# EST_MainV20_Input.net
KiCad netlist of a schematic drawn in Altium Designer
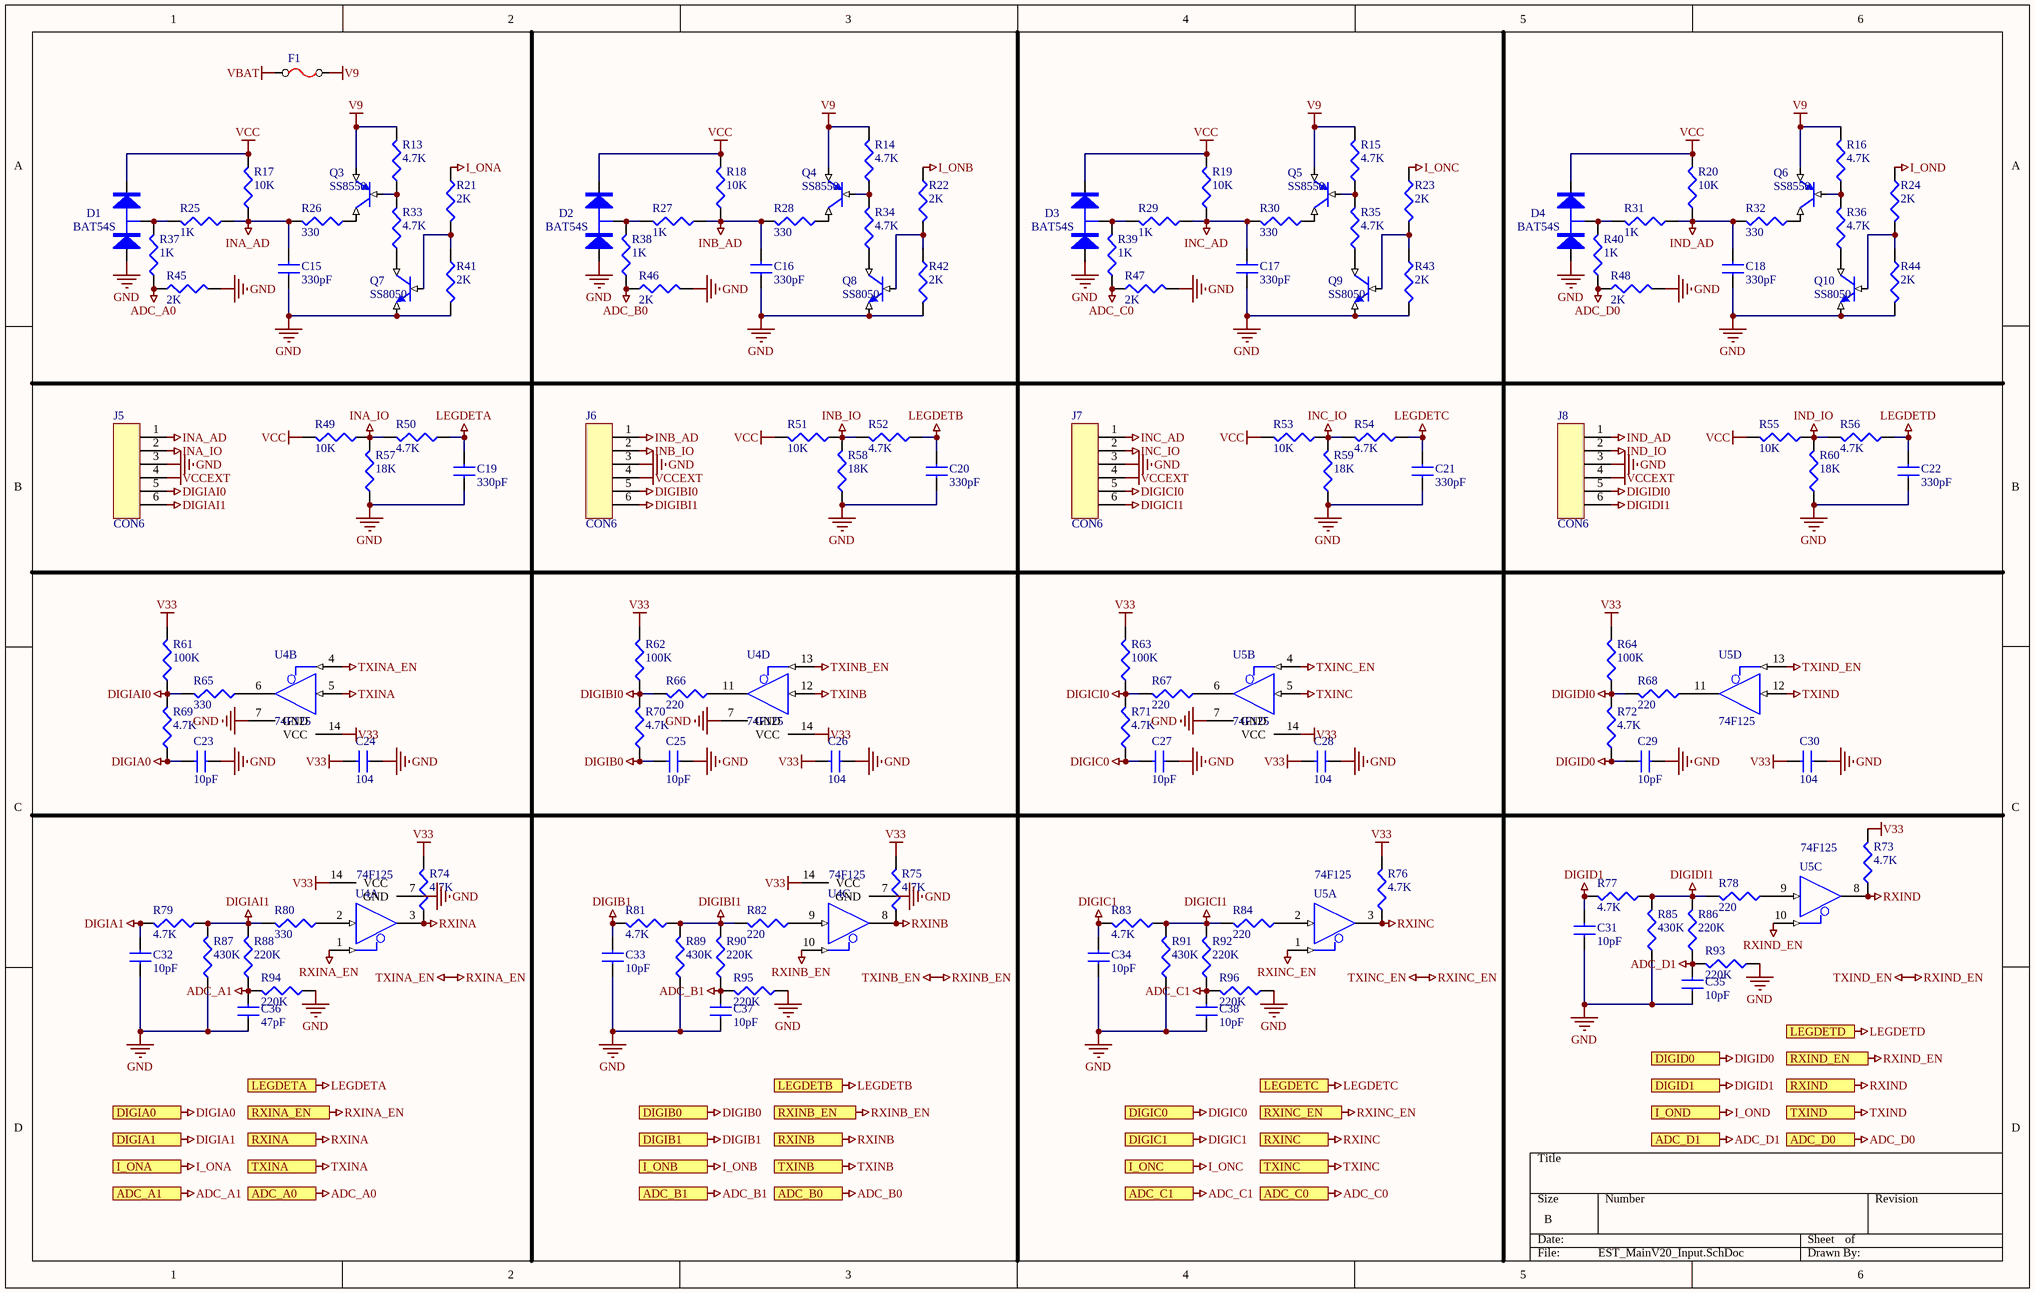
[diagram p0: EST_MainV20_Input.SchDoc]

(export (version "E")
  (design (tool "Eeschema 10.0.6"))
  (components
    (comp (ref "C15")
      (value "330pF")
      (footprint "CAP_0603")
      (description "Capacitor")
      (libsource (lib "模拟器件") (part "CAP"))
    )
    (comp (ref "C16")
      (value "330pF")
      (footprint "CAP_0603")
      (description "Capacitor")
      (libsource (lib "模拟器件") (part "CAP"))
    )
    (comp (ref "C17")
      (value "330pF")
      (footprint "CAP_0603")
      (description "Capacitor")
      (libsource (lib "模拟器件") (part "CAP"))
    )
    (comp (ref "C18")
      (value "330pF")
      (footprint "CAP_0603")
      (description "Capacitor")
      (libsource (lib "模拟器件") (part "CAP"))
    )
    (comp (ref "C19")
      (value "330pF")
      (footprint "CAP_0603")
      (description "Capacitor")
      (libsource (lib "模拟器件") (part "CAP"))
    )
    (comp (ref "C20")
      (value "330pF")
      (footprint "CAP_0603")
      (description "Capacitor")
      (libsource (lib "模拟器件") (part "CAP"))
    )
    (comp (ref "C21")
      (value "330pF")
      (footprint "CAP_0603")
      (description "Capacitor")
      (libsource (lib "模拟器件") (part "CAP"))
    )
    (comp (ref "C22")
      (value "330pF")
      (footprint "CAP_0603")
      (description "Capacitor")
      (libsource (lib "模拟器件") (part "CAP"))
    )
    (comp (ref "C23")
      (value "10pF")
      (footprint "CAP_0603")
      (description "Capacitor")
      (libsource (lib "模拟器件") (part "CAP"))
    )
    (comp (ref "C24")
      (value "104")
      (footprint "CAP_0603")
      (description "Capacitor")
      (libsource (lib "模拟器件") (part "CAP"))
    )
    (comp (ref "C25")
      (value "10pF")
      (footprint "CAP_0603")
      (description "Capacitor")
      (libsource (lib "模拟器件") (part "CAP"))
    )
    (comp (ref "C26")
      (value "104")
      (footprint "CAP_0603")
      (description "Capacitor")
      (libsource (lib "模拟器件") (part "CAP"))
    )
    (comp (ref "C27")
      (value "10pF")
      (footprint "CAP_0603")
      (description "Capacitor")
      (libsource (lib "模拟器件") (part "CAP"))
    )
    (comp (ref "C28")
      (value "104")
      (footprint "CAP_0603")
      (description "Capacitor")
      (libsource (lib "模拟器件") (part "CAP"))
    )
    (comp (ref "C29")
      (value "10pF")
      (footprint "CAP_0603")
      (description "Capacitor")
      (libsource (lib "模拟器件") (part "CAP"))
    )
    (comp (ref "C30")
      (value "104")
      (footprint "CAP_0603")
      (description "Capacitor")
      (libsource (lib "模拟器件") (part "CAP"))
    )
    (comp (ref "C31")
      (value "10pF")
      (footprint "CAP_0603")
      (description "Capacitor")
      (libsource (lib "模拟器件") (part "CAP"))
    )
    (comp (ref "C32")
      (value "10pF")
      (footprint "CAP_0603")
      (description "Capacitor")
      (libsource (lib "模拟器件") (part "CAP"))
    )
    (comp (ref "C33")
      (value "10pF")
      (footprint "CAP_0603")
      (description "Capacitor")
      (libsource (lib "模拟器件") (part "CAP"))
    )
    (comp (ref "C34")
      (value "10pF")
      (footprint "CAP_0603")
      (description "Capacitor")
      (libsource (lib "模拟器件") (part "CAP"))
    )
    (comp (ref "C35")
      (value "10pF")
      (footprint "CAP_0603")
      (description "Capacitor")
      (libsource (lib "模拟器件") (part "CAP"))
    )
    (comp (ref "C36")
      (value "47pF")
      (footprint "CAP_0603")
      (description "Capacitor")
      (libsource (lib "模拟器件") (part "CAP"))
    )
    (comp (ref "C37")
      (value "10pF")
      (footprint "CAP_0603")
      (description "Capacitor")
      (libsource (lib "模拟器件") (part "CAP"))
    )
    (comp (ref "C38")
      (value "10pF")
      (footprint "CAP_0603")
      (description "Capacitor")
      (libsource (lib "模拟器件") (part "CAP"))
    )
    (comp (ref "D1")
      (value "BAT54S")
      (footprint "BAT54S")
      (description "DIODE BRIDGE")
      (libsource (lib "模拟器件") (part "BANQIAO-A"))
    )
    (comp (ref "D2")
      (value "BAT54S")
      (footprint "BAT54S")
      (description "DIODE BRIDGE")
      (libsource (lib "模拟器件") (part "BANQIAO-A"))
    )
    (comp (ref "D3")
      (value "BAT54S")
      (footprint "BAT54S")
      (description "DIODE BRIDGE")
      (libsource (lib "模拟器件") (part "BANQIAO-A"))
    )
    (comp (ref "D4")
      (value "BAT54S")
      (footprint "BAT54S")
      (description "DIODE BRIDGE")
      (libsource (lib "模拟器件") (part "BANQIAO-A"))
    )
    (comp (ref "F1")
      (value "FUSE")
      (footprint "1812")
      (description "Fuse")
      (libsource (lib "模拟器件") (part "FUSE"))
    )
    (comp (ref "J5") (value "CON6") (footprint "Lego_RJ11") (libsource (lib "模拟器件") (part "CON6")))
    (comp (ref "J6") (value "CON6") (footprint "Lego_RJ11") (libsource (lib "模拟器件") (part "CON6")))
    (comp (ref "J7") (value "CON6") (footprint "Lego_RJ11") (libsource (lib "模拟器件") (part "CON6")))
    (comp (ref "J8") (value "CON6") (footprint "Lego_RJ11") (libsource (lib "模拟器件") (part "CON6")))
    (comp (ref "Q3")
      (value "SS8550")
      (footprint "8050SMD")
      (description "triode")
      (libsource (lib "模拟器件") (part "PNP"))
    )
    (comp (ref "Q4")
      (value "SS8550")
      (footprint "8050SMD")
      (description "triode")
      (libsource (lib "模拟器件") (part "PNP"))
    )
    (comp (ref "Q5")
      (value "SS8550")
      (footprint "8050SMD")
      (description "triode")
      (libsource (lib "模拟器件") (part "PNP"))
    )
    (comp (ref "Q6")
      (value "SS8550")
      (footprint "8050SMD")
      (description "triode")
      (libsource (lib "模拟器件") (part "PNP"))
    )
    (comp (ref "Q7")
      (value "SS8050")
      (footprint "8050SMD")
      (description "triode")
      (libsource (lib "模拟器件") (part "NPN"))
    )
    (comp (ref "Q8")
      (value "SS8050")
      (footprint "8050SMD")
      (description "triode")
      (libsource (lib "模拟器件") (part "NPN"))
    )
    (comp (ref "Q9")
      (value "SS8050")
      (footprint "8050SMD")
      (description "triode")
      (libsource (lib "模拟器件") (part "NPN"))
    )
    (comp (ref "Q10")
      (value "SS8050")
      (footprint "8050SMD")
      (description "triode")
      (libsource (lib "模拟器件") (part "NPN"))
    )
    (comp (ref "R13")
      (value "4.7K")
      (footprint "RES_0603")
      (description "Resistor")
      (libsource (lib "模拟器件") (part "RES"))
    )
    (comp (ref "R14")
      (value "4.7K")
      (footprint "RES_0603")
      (description "Resistor")
      (libsource (lib "模拟器件") (part "RES"))
    )
    (comp (ref "R15")
      (value "4.7K")
      (footprint "RES_0603")
      (description "Resistor")
      (libsource (lib "模拟器件") (part "RES"))
    )
    (comp (ref "R16")
      (value "4.7K")
      (footprint "RES_0603")
      (description "Resistor")
      (libsource (lib "模拟器件") (part "RES"))
    )
    (comp (ref "R17")
      (value "10K")
      (footprint "RES_0603")
      (description "Resistor")
      (libsource (lib "模拟器件") (part "RES"))
    )
    (comp (ref "R18")
      (value "10K")
      (footprint "RES_0603")
      (description "Resistor")
      (libsource (lib "模拟器件") (part "RES"))
    )
    (comp (ref "R19")
      (value "10K")
      (footprint "RES_0603")
      (description "Resistor")
      (libsource (lib "模拟器件") (part "RES"))
    )
    (comp (ref "R20")
      (value "10K")
      (footprint "RES_0603")
      (description "Resistor")
      (libsource (lib "模拟器件") (part "RES"))
    )
    (comp (ref "R21")
      (value "2K")
      (footprint "RES_0603")
      (description "Resistor")
      (libsource (lib "模拟器件") (part "RES"))
    )
    (comp (ref "R22")
      (value "2K")
      (footprint "RES_0603")
      (description "Resistor")
      (libsource (lib "模拟器件") (part "RES"))
    )
    (comp (ref "R23")
      (value "2K")
      (footprint "RES_0603")
      (description "Resistor")
      (libsource (lib "模拟器件") (part "RES"))
    )
    (comp (ref "R24")
      (value "2K")
      (footprint "RES_0603")
      (description "Resistor")
      (libsource (lib "模拟器件") (part "RES"))
    )
    (comp (ref "R25")
      (value "1K")
      (footprint "RES_0603")
      (description "Resistor")
      (libsource (lib "模拟器件") (part "RES"))
    )
    (comp (ref "R26")
      (value "330")
      (footprint "RES_0603")
      (description "Resistor")
      (libsource (lib "模拟器件") (part "RES"))
    )
    (comp (ref "R27")
      (value "1K")
      (footprint "RES_0603")
      (description "Resistor")
      (libsource (lib "模拟器件") (part "RES"))
    )
    (comp (ref "R28")
      (value "330")
      (footprint "RES_0603")
      (description "Resistor")
      (libsource (lib "模拟器件") (part "RES"))
    )
    (comp (ref "R29")
      (value "1K")
      (footprint "RES_0603")
      (description "Resistor")
      (libsource (lib "模拟器件") (part "RES"))
    )
    (comp (ref "R30")
      (value "330")
      (footprint "RES_0603")
      (description "Resistor")
      (libsource (lib "模拟器件") (part "RES"))
    )
    (comp (ref "R31")
      (value "1K")
      (footprint "RES_0603")
      (description "Resistor")
      (libsource (lib "模拟器件") (part "RES"))
    )
    (comp (ref "R32")
      (value "330")
      (footprint "RES_0603")
      (description "Resistor")
      (libsource (lib "模拟器件") (part "RES"))
    )
    (comp (ref "R33")
      (value "4.7K")
      (footprint "RES_0603")
      (description "Resistor")
      (libsource (lib "模拟器件") (part "RES"))
    )
    (comp (ref "R34")
      (value "4.7K")
      (footprint "RES_0603")
      (description "Resistor")
      (libsource (lib "模拟器件") (part "RES"))
    )
    (comp (ref "R35")
      (value "4.7K")
      (footprint "RES_0603")
      (description "Resistor")
      (libsource (lib "模拟器件") (part "RES"))
    )
    (comp (ref "R36")
      (value "4.7K")
      (footprint "RES_0603")
      (description "Resistor")
      (libsource (lib "模拟器件") (part "RES"))
    )
    (comp (ref "R37")
      (value "1K")
      (footprint "RES_0603")
      (description "Resistor")
      (libsource (lib "模拟器件") (part "RES"))
    )
    (comp (ref "R38")
      (value "1K")
      (footprint "RES_0603")
      (description "Resistor")
      (libsource (lib "模拟器件") (part "RES"))
    )
    (comp (ref "R39")
      (value "1K")
      (footprint "RES_0603")
      (description "Resistor")
      (libsource (lib "模拟器件") (part "RES"))
    )
    (comp (ref "R40")
      (value "1K")
      (footprint "RES_0603")
      (description "Resistor")
      (libsource (lib "模拟器件") (part "RES"))
    )
    (comp (ref "R41")
      (value "2K")
      (footprint "RES_0603")
      (description "Resistor")
      (libsource (lib "模拟器件") (part "RES"))
    )
    (comp (ref "R42")
      (value "2K")
      (footprint "RES_0603")
      (description "Resistor")
      (libsource (lib "模拟器件") (part "RES"))
    )
    (comp (ref "R43")
      (value "2K")
      (footprint "RES_0603")
      (description "Resistor")
      (libsource (lib "模拟器件") (part "RES"))
    )
    (comp (ref "R44")
      (value "2K")
      (footprint "RES_0603")
      (description "Resistor")
      (libsource (lib "模拟器件") (part "RES"))
    )
    (comp (ref "R45")
      (value "2K")
      (footprint "RES_0603")
      (description "Resistor")
      (libsource (lib "模拟器件") (part "RES"))
    )
    (comp (ref "R46")
      (value "2K")
      (footprint "RES_0603")
      (description "Resistor")
      (libsource (lib "模拟器件") (part "RES"))
    )
    (comp (ref "R47")
      (value "2K")
      (footprint "RES_0603")
      (description "Resistor")
      (libsource (lib "模拟器件") (part "RES"))
    )
    (comp (ref "R48")
      (value "2K")
      (footprint "RES_0603")
      (description "Resistor")
      (libsource (lib "模拟器件") (part "RES"))
    )
    (comp (ref "R49")
      (value "10K")
      (footprint "RES_0603")
      (description "Resistor")
      (libsource (lib "模拟器件") (part "RES"))
    )
    (comp (ref "R50")
      (value "4.7K")
      (footprint "RES_0603")
      (description "Resistor")
      (libsource (lib "模拟器件") (part "RES"))
    )
    (comp (ref "R51")
      (value "10K")
      (footprint "RES_0603")
      (description "Resistor")
      (libsource (lib "模拟器件") (part "RES"))
    )
    (comp (ref "R52")
      (value "4.7K")
      (footprint "RES_0603")
      (description "Resistor")
      (libsource (lib "模拟器件") (part "RES"))
    )
    (comp (ref "R53")
      (value "10K")
      (footprint "RES_0603")
      (description "Resistor")
      (libsource (lib "模拟器件") (part "RES"))
    )
    (comp (ref "R54")
      (value "4.7K")
      (footprint "RES_0603")
      (description "Resistor")
      (libsource (lib "模拟器件") (part "RES"))
    )
    (comp (ref "R55")
      (value "10K")
      (footprint "RES_0603")
      (description "Resistor")
      (libsource (lib "模拟器件") (part "RES"))
    )
    (comp (ref "R56")
      (value "4.7K")
      (footprint "RES_0603")
      (description "Resistor")
      (libsource (lib "模拟器件") (part "RES"))
    )
    (comp (ref "R57")
      (value "18K")
      (footprint "RES_0603")
      (description "Resistor")
      (libsource (lib "模拟器件") (part "RES"))
    )
    (comp (ref "R58")
      (value "18K")
      (footprint "RES_0603")
      (description "Resistor")
      (libsource (lib "模拟器件") (part "RES"))
    )
    (comp (ref "R59")
      (value "18K")
      (footprint "RES_0603")
      (description "Resistor")
      (libsource (lib "模拟器件") (part "RES"))
    )
    (comp (ref "R60")
      (value "18K")
      (footprint "RES_0603")
      (description "Resistor")
      (libsource (lib "模拟器件") (part "RES"))
    )
    (comp (ref "R61")
      (value "100K")
      (footprint "RES_0603")
      (description "Resistor")
      (libsource (lib "模拟器件") (part "RES"))
    )
    (comp (ref "R62")
      (value "100K")
      (footprint "RES_0603")
      (description "Resistor")
      (libsource (lib "模拟器件") (part "RES"))
    )
    (comp (ref "R63")
      (value "100K")
      (footprint "RES_0603")
      (description "Resistor")
      (libsource (lib "模拟器件") (part "RES"))
    )
    (comp (ref "R64")
      (value "100K")
      (footprint "RES_0603")
      (description "Resistor")
      (libsource (lib "模拟器件") (part "RES"))
    )
    (comp (ref "R65")
      (value "330")
      (footprint "RES_0603")
      (description "Resistor")
      (libsource (lib "模拟器件") (part "RES"))
    )
    (comp (ref "R66")
      (value "220")
      (footprint "RES_0603")
      (description "Resistor")
      (libsource (lib "模拟器件") (part "RES"))
    )
    (comp (ref "R67")
      (value "220")
      (footprint "RES_0603")
      (description "Resistor")
      (libsource (lib "模拟器件") (part "RES"))
    )
    (comp (ref "R68")
      (value "220")
      (footprint "RES_0603")
      (description "Resistor")
      (libsource (lib "模拟器件") (part "RES"))
    )
    (comp (ref "R69")
      (value "4.7K")
      (footprint "RES_0603")
      (description "Resistor")
      (libsource (lib "模拟器件") (part "RES"))
    )
    (comp (ref "R70")
      (value "4.7K")
      (footprint "RES_0603")
      (description "Resistor")
      (libsource (lib "模拟器件") (part "RES"))
    )
    (comp (ref "R71")
      (value "4.7K")
      (footprint "RES_0603")
      (description "Resistor")
      (libsource (lib "模拟器件") (part "RES"))
    )
    (comp (ref "R72")
      (value "4.7K")
      (footprint "RES_0603")
      (description "Resistor")
      (libsource (lib "模拟器件") (part "RES"))
    )
    (comp (ref "R73")
      (value "4.7K")
      (footprint "RES_0603")
      (description "Resistor")
      (libsource (lib "模拟器件") (part "RES"))
    )
    (comp (ref "R74")
      (value "4.7K")
      (footprint "RES_0603")
      (description "Resistor")
      (libsource (lib "模拟器件") (part "RES"))
    )
    (comp (ref "R75")
      (value "4.7K")
      (footprint "RES_0603")
      (description "Resistor")
      (libsource (lib "模拟器件") (part "RES"))
    )
    (comp (ref "R76")
      (value "4.7K")
      (footprint "RES_0603")
      (description "Resistor")
      (libsource (lib "模拟器件") (part "RES"))
    )
    (comp (ref "R77")
      (value "4.7K")
      (footprint "RES_0603")
      (description "Resistor")
      (libsource (lib "模拟器件") (part "RES"))
    )
    (comp (ref "R78")
      (value "220")
      (footprint "RES_0603")
      (description "Resistor")
      (libsource (lib "模拟器件") (part "RES"))
    )
    (comp (ref "R79")
      (value "4.7K")
      (footprint "RES_0603")
      (description "Resistor")
      (libsource (lib "模拟器件") (part "RES"))
    )
    (comp (ref "R80")
      (value "330")
      (footprint "RES_0603")
      (description "Resistor")
      (libsource (lib "模拟器件") (part "RES"))
    )
    (comp (ref "R81")
      (value "4.7K")
      (footprint "RES_0603")
      (description "Resistor")
      (libsource (lib "模拟器件") (part "RES"))
    )
    (comp (ref "R82")
      (value "220")
      (footprint "RES_0603")
      (description "Resistor")
      (libsource (lib "模拟器件") (part "RES"))
    )
    (comp (ref "R83")
      (value "4.7K")
      (footprint "RES_0603")
      (description "Resistor")
      (libsource (lib "模拟器件") (part "RES"))
    )
    (comp (ref "R84")
      (value "220")
      (footprint "RES_0603")
      (description "Resistor")
      (libsource (lib "模拟器件") (part "RES"))
    )
    (comp (ref "R85")
      (value "430K")
      (footprint "RES_0603")
      (description "Resistor")
      (libsource (lib "模拟器件") (part "RES"))
    )
    (comp (ref "R86")
      (value "220K")
      (footprint "RES_0603")
      (description "Resistor")
      (libsource (lib "模拟器件") (part "RES"))
    )
    (comp (ref "R87")
      (value "430K")
      (footprint "RES_0603")
      (description "Resistor")
      (libsource (lib "模拟器件") (part "RES"))
    )
    (comp (ref "R88")
      (value "220K")
      (footprint "RES_0603")
      (description "Resistor")
      (libsource (lib "模拟器件") (part "RES"))
    )
    (comp (ref "R89")
      (value "430K")
      (footprint "RES_0603")
      (description "Resistor")
      (libsource (lib "模拟器件") (part "RES"))
    )
    (comp (ref "R90")
      (value "220K")
      (footprint "RES_0603")
      (description "Resistor")
      (libsource (lib "模拟器件") (part "RES"))
    )
    (comp (ref "R91")
      (value "430K")
      (footprint "RES_0603")
      (description "Resistor")
      (libsource (lib "模拟器件") (part "RES"))
    )
    (comp (ref "R92")
      (value "220K")
      (footprint "RES_0603")
      (description "Resistor")
      (libsource (lib "模拟器件") (part "RES"))
    )
    (comp (ref "R93")
      (value "220K")
      (footprint "RES_0603")
      (description "Resistor")
      (libsource (lib "模拟器件") (part "RES"))
    )
    (comp (ref "R94")
      (value "220K")
      (footprint "RES_0603")
      (description "Resistor")
      (libsource (lib "模拟器件") (part "RES"))
    )
    (comp (ref "R95")
      (value "220K")
      (footprint "RES_0603")
      (description "Resistor")
      (libsource (lib "模拟器件") (part "RES"))
    )
    (comp (ref "R96")
      (value "220K")
      (footprint "RES_0603")
      (description "Resistor")
      (libsource (lib "模拟器件") (part "RES"))
    )
    (comp (ref "U4")
      (value "74F125")
      (footprint "TSSOP14")
      (description "Quad Bus Buffer Gate with 3-State Output")
      (libsource (lib "TTL") (part "74F125"))
    )
    (comp (ref "U5")
      (value "74F125")
      (footprint "TSSOP14")
      (description "Quad Bus Buffer Gate with 3-State Output")
      (libsource (lib "TTL") (part "74F125"))
    )
  )
  (nets
    (net (code "1") (name "ADC_A0") (class "Default")
      (node (ref "R37") (pin "2") (pinfunction "BOT_2") (pintype "passive"))
      (node (ref "R45") (pin "2") (pinfunction "BOT_2") (pintype "passive"))
    )
    (net (code "2") (name "ADC_A1") (class "Default")
      (node (ref "C36") (pin "2") (pinfunction "2_2") (pintype "passive"))
      (node (ref "R88") (pin "2") (pinfunction "BOT_2") (pintype "passive"))
      (node (ref "R94") (pin "1") (pinfunction "TOP_1") (pintype "passive"))
    )
    (net (code "3") (name "ADC_B0") (class "Default")
      (node (ref "R38") (pin "2") (pinfunction "BOT_2") (pintype "passive"))
      (node (ref "R46") (pin "2") (pinfunction "BOT_2") (pintype "passive"))
    )
    (net (code "4") (name "ADC_B1") (class "Default")
      (node (ref "C37") (pin "2") (pinfunction "2_2") (pintype "passive"))
      (node (ref "R90") (pin "2") (pinfunction "BOT_2") (pintype "passive"))
      (node (ref "R95") (pin "1") (pinfunction "TOP_1") (pintype "passive"))
    )
    (net (code "5") (name "ADC_C0") (class "Default")
      (node (ref "R39") (pin "2") (pinfunction "BOT_2") (pintype "passive"))
      (node (ref "R47") (pin "2") (pinfunction "BOT_2") (pintype "passive"))
    )
    (net (code "6") (name "ADC_C1") (class "Default")
      (node (ref "C38") (pin "2") (pinfunction "2_2") (pintype "passive"))
      (node (ref "R92") (pin "2") (pinfunction "BOT_2") (pintype "passive"))
      (node (ref "R96") (pin "1") (pinfunction "TOP_1") (pintype "passive"))
    )
    (net (code "7") (name "ADC_D0") (class "Default")
      (node (ref "R40") (pin "2") (pinfunction "BOT_2") (pintype "passive"))
      (node (ref "R48") (pin "2") (pinfunction "BOT_2") (pintype "passive"))
    )
    (net (code "8") (name "ADC_D1") (class "Default")
      (node (ref "C35") (pin "2") (pinfunction "2_2") (pintype "passive"))
      (node (ref "R86") (pin "2") (pinfunction "BOT_2") (pintype "passive"))
      (node (ref "R93") (pin "1") (pinfunction "TOP_1") (pintype "passive"))
    )
    (net (code "9") (name "DIGIA0") (class "Default")
      (node (ref "C23") (pin "1") (pinfunction "1_1") (pintype "passive"))
      (node (ref "R69") (pin "2") (pinfunction "BOT_2") (pintype "passive"))
    )
    (net (code "10") (name "DIGIA1") (class "Default")
      (node (ref "C32") (pin "2") (pinfunction "2_2") (pintype "passive"))
      (node (ref "R79") (pin "1") (pinfunction "TOP_1") (pintype "passive"))
    )
    (net (code "11") (name "DIGIAI0") (class "Default")
      (node (ref "J5") (pin "5") (pinfunction "5_5") (pintype "passive"))
      (node (ref "R61") (pin "2") (pinfunction "BOT_2") (pintype "passive"))
      (node (ref "R65") (pin "1") (pinfunction "TOP_1") (pintype "passive"))
      (node (ref "R69") (pin "1") (pinfunction "TOP_1") (pintype "passive"))
    )
    (net (code "12") (name "DIGIAI1") (class "Default")
      (node (ref "J5") (pin "6") (pinfunction "6_6") (pintype "passive"))
      (node (ref "R79") (pin "2") (pinfunction "BOT_2") (pintype "passive"))
      (node (ref "R80") (pin "1") (pinfunction "TOP_1") (pintype "passive"))
      (node (ref "R87") (pin "1") (pinfunction "TOP_1") (pintype "passive"))
      (node (ref "R88") (pin "1") (pinfunction "TOP_1") (pintype "passive"))
    )
    (net (code "13") (name "DIGIB0") (class "Default")
      (node (ref "C25") (pin "1") (pinfunction "1_1") (pintype "passive"))
      (node (ref "R70") (pin "2") (pinfunction "BOT_2") (pintype "passive"))
    )
    (net (code "14") (name "DIGIB1") (class "Default")
      (node (ref "C33") (pin "2") (pinfunction "2_2") (pintype "passive"))
      (node (ref "R81") (pin "1") (pinfunction "TOP_1") (pintype "passive"))
    )
    (net (code "15") (name "DIGIBI0") (class "Default")
      (node (ref "J6") (pin "5") (pinfunction "5_5") (pintype "passive"))
      (node (ref "R62") (pin "2") (pinfunction "BOT_2") (pintype "passive"))
      (node (ref "R66") (pin "1") (pinfunction "TOP_1") (pintype "passive"))
      (node (ref "R70") (pin "1") (pinfunction "TOP_1") (pintype "passive"))
    )
    (net (code "16") (name "DIGIBI1") (class "Default")
      (node (ref "J6") (pin "6") (pinfunction "6_6") (pintype "passive"))
      (node (ref "R81") (pin "2") (pinfunction "BOT_2") (pintype "passive"))
      (node (ref "R82") (pin "1") (pinfunction "TOP_1") (pintype "passive"))
      (node (ref "R89") (pin "1") (pinfunction "TOP_1") (pintype "passive"))
      (node (ref "R90") (pin "1") (pinfunction "TOP_1") (pintype "passive"))
    )
    (net (code "17") (name "DIGIC0") (class "Default")
      (node (ref "C27") (pin "1") (pinfunction "1_1") (pintype "passive"))
      (node (ref "R71") (pin "2") (pinfunction "BOT_2") (pintype "passive"))
    )
    (net (code "18") (name "DIGIC1") (class "Default")
      (node (ref "C34") (pin "2") (pinfunction "2_2") (pintype "passive"))
      (node (ref "R83") (pin "1") (pinfunction "TOP_1") (pintype "passive"))
    )
    (net (code "19") (name "DIGICI0") (class "Default")
      (node (ref "J7") (pin "5") (pinfunction "5_5") (pintype "passive"))
      (node (ref "R63") (pin "2") (pinfunction "BOT_2") (pintype "passive"))
      (node (ref "R67") (pin "1") (pinfunction "TOP_1") (pintype "passive"))
      (node (ref "R71") (pin "1") (pinfunction "TOP_1") (pintype "passive"))
    )
    (net (code "20") (name "DIGICI1") (class "Default")
      (node (ref "J7") (pin "6") (pinfunction "6_6") (pintype "passive"))
      (node (ref "R83") (pin "2") (pinfunction "BOT_2") (pintype "passive"))
      (node (ref "R84") (pin "1") (pinfunction "TOP_1") (pintype "passive"))
      (node (ref "R91") (pin "1") (pinfunction "TOP_1") (pintype "passive"))
      (node (ref "R92") (pin "1") (pinfunction "TOP_1") (pintype "passive"))
    )
    (net (code "21") (name "DIGID0") (class "Default")
      (node (ref "C29") (pin "1") (pinfunction "1_1") (pintype "passive"))
      (node (ref "R72") (pin "2") (pinfunction "BOT_2") (pintype "passive"))
    )
    (net (code "22") (name "DIGID1") (class "Default")
      (node (ref "C31") (pin "2") (pinfunction "2_2") (pintype "passive"))
      (node (ref "R77") (pin "1") (pinfunction "TOP_1") (pintype "passive"))
    )
    (net (code "23") (name "DIGIDI0") (class "Default")
      (node (ref "J8") (pin "5") (pinfunction "5_5") (pintype "passive"))
      (node (ref "R64") (pin "2") (pinfunction "BOT_2") (pintype "passive"))
      (node (ref "R68") (pin "1") (pinfunction "TOP_1") (pintype "passive"))
      (node (ref "R72") (pin "1") (pinfunction "TOP_1") (pintype "passive"))
    )
    (net (code "24") (name "DIGIDI1") (class "Default")
      (node (ref "J8") (pin "6") (pinfunction "6_6") (pintype "passive"))
      (node (ref "R77") (pin "2") (pinfunction "BOT_2") (pintype "passive"))
      (node (ref "R78") (pin "1") (pinfunction "TOP_1") (pintype "passive"))
      (node (ref "R85") (pin "1") (pinfunction "TOP_1") (pintype "passive"))
      (node (ref "R86") (pin "1") (pinfunction "TOP_1") (pintype "passive"))
    )
    (net (code "25") (name "GND") (class "Default")
      (node (ref "C15") (pin "2") (pinfunction "2_2") (pintype "passive"))
      (node (ref "C16") (pin "2") (pinfunction "2_2") (pintype "passive"))
      (node (ref "C17") (pin "2") (pinfunction "2_2") (pintype "passive"))
      (node (ref "C18") (pin "2") (pinfunction "2_2") (pintype "passive"))
      (node (ref "C19") (pin "2") (pinfunction "2_2") (pintype "passive"))
      (node (ref "C20") (pin "2") (pinfunction "2_2") (pintype "passive"))
      (node (ref "C21") (pin "2") (pinfunction "2_2") (pintype "passive"))
      (node (ref "C22") (pin "2") (pinfunction "2_2") (pintype "passive"))
      (node (ref "C23") (pin "2") (pinfunction "2_2") (pintype "passive"))
      (node (ref "C24") (pin "2") (pinfunction "2_2") (pintype "passive"))
      (node (ref "C25") (pin "2") (pinfunction "2_2") (pintype "passive"))
      (node (ref "C26") (pin "2") (pinfunction "2_2") (pintype "passive"))
      (node (ref "C27") (pin "2") (pinfunction "2_2") (pintype "passive"))
      (node (ref "C28") (pin "2") (pinfunction "2_2") (pintype "passive"))
      (node (ref "C29") (pin "2") (pinfunction "2_2") (pintype "passive"))
      (node (ref "C30") (pin "2") (pinfunction "2_2") (pintype "passive"))
      (node (ref "C31") (pin "1") (pinfunction "1_1") (pintype "passive"))
      (node (ref "C32") (pin "1") (pinfunction "1_1") (pintype "passive"))
      (node (ref "C33") (pin "1") (pinfunction "1_1") (pintype "passive"))
      (node (ref "C34") (pin "1") (pinfunction "1_1") (pintype "passive"))
      (node (ref "C35") (pin "1") (pinfunction "1_1") (pintype "passive"))
      (node (ref "C36") (pin "1") (pinfunction "1_1") (pintype "passive"))
      (node (ref "C37") (pin "1") (pinfunction "1_1") (pintype "passive"))
      (node (ref "C38") (pin "1") (pinfunction "1_1") (pintype "passive"))
      (node (ref "D1") (pin "1") (pinfunction "A_1") (pintype "passive"))
      (node (ref "D2") (pin "1") (pinfunction "A_1") (pintype "passive"))
      (node (ref "D3") (pin "1") (pinfunction "A_1") (pintype "passive"))
      (node (ref "D4") (pin "1") (pinfunction "A_1") (pintype "passive"))
      (node (ref "J5") (pin "3") (pinfunction "3_3") (pintype "passive"))
      (node (ref "J6") (pin "3") (pinfunction "3_3") (pintype "passive"))
      (node (ref "J7") (pin "3") (pinfunction "3_3") (pintype "passive"))
      (node (ref "J8") (pin "3") (pinfunction "3_3") (pintype "passive"))
      (node (ref "Q10") (pin "1") (pinfunction "E_1") (pintype "input"))
      (node (ref "Q7") (pin "1") (pinfunction "E_1") (pintype "input"))
      (node (ref "Q8") (pin "1") (pinfunction "E_1") (pintype "input"))
      (node (ref "Q9") (pin "1") (pinfunction "E_1") (pintype "input"))
      (node (ref "R41") (pin "1") (pinfunction "TOP_1") (pintype "passive"))
      (node (ref "R42") (pin "1") (pinfunction "TOP_1") (pintype "passive"))
      (node (ref "R43") (pin "1") (pinfunction "TOP_1") (pintype "passive"))
      (node (ref "R44") (pin "1") (pinfunction "TOP_1") (pintype "passive"))
      (node (ref "R45") (pin "1") (pinfunction "TOP_1") (pintype "passive"))
      (node (ref "R46") (pin "1") (pinfunction "TOP_1") (pintype "passive"))
      (node (ref "R47") (pin "1") (pinfunction "TOP_1") (pintype "passive"))
      (node (ref "R48") (pin "1") (pinfunction "TOP_1") (pintype "passive"))
      (node (ref "R57") (pin "2") (pinfunction "BOT_2") (pintype "passive"))
      (node (ref "R58") (pin "2") (pinfunction "BOT_2") (pintype "passive"))
      (node (ref "R59") (pin "2") (pinfunction "BOT_2") (pintype "passive"))
      (node (ref "R60") (pin "2") (pinfunction "BOT_2") (pintype "passive"))
      (node (ref "R85") (pin "2") (pinfunction "BOT_2") (pintype "passive"))
      (node (ref "R87") (pin "2") (pinfunction "BOT_2") (pintype "passive"))
      (node (ref "R89") (pin "2") (pinfunction "BOT_2") (pintype "passive"))
      (node (ref "R91") (pin "2") (pinfunction "BOT_2") (pintype "passive"))
      (node (ref "R93") (pin "2") (pinfunction "BOT_2") (pintype "passive"))
      (node (ref "R94") (pin "2") (pinfunction "BOT_2") (pintype "passive"))
      (node (ref "R95") (pin "2") (pinfunction "BOT_2") (pintype "passive"))
      (node (ref "R96") (pin "2") (pinfunction "BOT_2") (pintype "passive"))
      (node (ref "U4") (pin "7") (pinfunction "GND_7") (pintype "power_in"))
      (node (ref "U5") (pin "7") (pinfunction "GND_7") (pintype "power_in"))
    )
    (net (code "26") (name "INA_AD") (class "Default")
      (node (ref "C15") (pin "1") (pinfunction "1_1") (pintype "passive"))
      (node (ref "J5") (pin "1") (pinfunction "1_1") (pintype "passive"))
      (node (ref "R17") (pin "2") (pinfunction "BOT_2") (pintype "passive"))
      (node (ref "R25") (pin "2") (pinfunction "BOT_2") (pintype "passive"))
      (node (ref "R26") (pin "1") (pinfunction "TOP_1") (pintype "passive"))
    )
    (net (code "27") (name "INA_IO") (class "Default")
      (node (ref "J5") (pin "2") (pinfunction "2_2") (pintype "passive"))
      (node (ref "R49") (pin "2") (pinfunction "BOT_2") (pintype "passive"))
      (node (ref "R50") (pin "1") (pinfunction "TOP_1") (pintype "passive"))
      (node (ref "R57") (pin "1") (pinfunction "TOP_1") (pintype "passive"))
    )
    (net (code "28") (name "INB_AD") (class "Default")
      (node (ref "C16") (pin "1") (pinfunction "1_1") (pintype "passive"))
      (node (ref "J6") (pin "1") (pinfunction "1_1") (pintype "passive"))
      (node (ref "R18") (pin "2") (pinfunction "BOT_2") (pintype "passive"))
      (node (ref "R27") (pin "2") (pinfunction "BOT_2") (pintype "passive"))
      (node (ref "R28") (pin "1") (pinfunction "TOP_1") (pintype "passive"))
    )
    (net (code "29") (name "INB_IO") (class "Default")
      (node (ref "J6") (pin "2") (pinfunction "2_2") (pintype "passive"))
      (node (ref "R51") (pin "2") (pinfunction "BOT_2") (pintype "passive"))
      (node (ref "R52") (pin "1") (pinfunction "TOP_1") (pintype "passive"))
      (node (ref "R58") (pin "1") (pinfunction "TOP_1") (pintype "passive"))
    )
    (net (code "30") (name "INC_AD") (class "Default")
      (node (ref "C17") (pin "1") (pinfunction "1_1") (pintype "passive"))
      (node (ref "J7") (pin "1") (pinfunction "1_1") (pintype "passive"))
      (node (ref "R19") (pin "2") (pinfunction "BOT_2") (pintype "passive"))
      (node (ref "R29") (pin "2") (pinfunction "BOT_2") (pintype "passive"))
      (node (ref "R30") (pin "1") (pinfunction "TOP_1") (pintype "passive"))
    )
    (net (code "31") (name "INC_IO") (class "Default")
      (node (ref "J7") (pin "2") (pinfunction "2_2") (pintype "passive"))
      (node (ref "R53") (pin "2") (pinfunction "BOT_2") (pintype "passive"))
      (node (ref "R54") (pin "1") (pinfunction "TOP_1") (pintype "passive"))
      (node (ref "R59") (pin "1") (pinfunction "TOP_1") (pintype "passive"))
    )
    (net (code "32") (name "IND_AD") (class "Default")
      (node (ref "C18") (pin "1") (pinfunction "1_1") (pintype "passive"))
      (node (ref "J8") (pin "1") (pinfunction "1_1") (pintype "passive"))
      (node (ref "R20") (pin "2") (pinfunction "BOT_2") (pintype "passive"))
      (node (ref "R31") (pin "2") (pinfunction "BOT_2") (pintype "passive"))
      (node (ref "R32") (pin "1") (pinfunction "TOP_1") (pintype "passive"))
    )
    (net (code "33") (name "IND_IO") (class "Default")
      (node (ref "J8") (pin "2") (pinfunction "2_2") (pintype "passive"))
      (node (ref "R55") (pin "2") (pinfunction "BOT_2") (pintype "passive"))
      (node (ref "R56") (pin "1") (pinfunction "TOP_1") (pintype "passive"))
      (node (ref "R60") (pin "1") (pinfunction "TOP_1") (pintype "passive"))
    )
    (net (code "34") (name "I_ONA") (class "Default")
      (node (ref "R21") (pin "2") (pinfunction "BOT_2") (pintype "passive"))
    )
    (net (code "35") (name "I_ONB") (class "Default")
      (node (ref "R22") (pin "2") (pinfunction "BOT_2") (pintype "passive"))
    )
    (net (code "36") (name "I_ONC") (class "Default")
      (node (ref "R23") (pin "2") (pinfunction "BOT_2") (pintype "passive"))
    )
    (net (code "37") (name "I_OND") (class "Default")
      (node (ref "R24") (pin "2") (pinfunction "BOT_2") (pintype "passive"))
    )
    (net (code "38") (name "LEGDETA") (class "Default")
      (node (ref "C19") (pin "1") (pinfunction "1_1") (pintype "passive"))
      (node (ref "R50") (pin "2") (pinfunction "BOT_2") (pintype "passive"))
    )
    (net (code "39") (name "LEGDETB") (class "Default")
      (node (ref "C20") (pin "1") (pinfunction "1_1") (pintype "passive"))
      (node (ref "R52") (pin "2") (pinfunction "BOT_2") (pintype "passive"))
    )
    (net (code "40") (name "LEGDETC") (class "Default")
      (node (ref "C21") (pin "1") (pinfunction "1_1") (pintype "passive"))
      (node (ref "R54") (pin "2") (pinfunction "BOT_2") (pintype "passive"))
    )
    (net (code "41") (name "LEGDETD") (class "Default")
      (node (ref "C22") (pin "1") (pinfunction "1_1") (pintype "passive"))
      (node (ref "R56") (pin "2") (pinfunction "BOT_2") (pintype "passive"))
    )
    (net (code "42") (name "Net-(D1-C)") (class "Default")
      (node (ref "D1") (pin "2") (pinfunction "C_2") (pintype "passive"))
      (node (ref "R25") (pin "1") (pinfunction "TOP_1") (pintype "passive"))
      (node (ref "R37") (pin "1") (pinfunction "TOP_1") (pintype "passive"))
    )
    (net (code "43") (name "Net-(D2-C)") (class "Default")
      (node (ref "D2") (pin "2") (pinfunction "C_2") (pintype "passive"))
      (node (ref "R27") (pin "1") (pinfunction "TOP_1") (pintype "passive"))
      (node (ref "R38") (pin "1") (pinfunction "TOP_1") (pintype "passive"))
    )
    (net (code "44") (name "Net-(D3-C)") (class "Default")
      (node (ref "D3") (pin "2") (pinfunction "C_2") (pintype "passive"))
      (node (ref "R29") (pin "1") (pinfunction "TOP_1") (pintype "passive"))
      (node (ref "R39") (pin "1") (pinfunction "TOP_1") (pintype "passive"))
    )
    (net (code "45") (name "Net-(D4-C)") (class "Default")
      (node (ref "D4") (pin "2") (pinfunction "C_2") (pintype "passive"))
      (node (ref "R31") (pin "1") (pinfunction "TOP_1") (pintype "passive"))
      (node (ref "R40") (pin "1") (pinfunction "TOP_1") (pintype "passive"))
    )
    (net (code "46") (name "Net-(Q3-B)") (class "Default")
      (node (ref "Q3") (pin "2") (pinfunction "B_2") (pintype "input"))
      (node (ref "R13") (pin "2") (pinfunction "BOT_2") (pintype "passive"))
      (node (ref "R33") (pin "1") (pinfunction "TOP_1") (pintype "passive"))
    )
    (net (code "47") (name "Net-(Q3-C)") (class "Default")
      (node (ref "Q3") (pin "3") (pinfunction "C_3") (pintype "input"))
      (node (ref "R26") (pin "2") (pinfunction "BOT_2") (pintype "passive"))
    )
    (net (code "48") (name "Net-(Q4-B)") (class "Default")
      (node (ref "Q4") (pin "2") (pinfunction "B_2") (pintype "input"))
      (node (ref "R14") (pin "2") (pinfunction "BOT_2") (pintype "passive"))
      (node (ref "R34") (pin "1") (pinfunction "TOP_1") (pintype "passive"))
    )
    (net (code "49") (name "Net-(Q4-C)") (class "Default")
      (node (ref "Q4") (pin "3") (pinfunction "C_3") (pintype "input"))
      (node (ref "R28") (pin "2") (pinfunction "BOT_2") (pintype "passive"))
    )
    (net (code "50") (name "Net-(Q5-B)") (class "Default")
      (node (ref "Q5") (pin "2") (pinfunction "B_2") (pintype "input"))
      (node (ref "R15") (pin "2") (pinfunction "BOT_2") (pintype "passive"))
      (node (ref "R35") (pin "1") (pinfunction "TOP_1") (pintype "passive"))
    )
    (net (code "51") (name "Net-(Q5-C)") (class "Default")
      (node (ref "Q5") (pin "3") (pinfunction "C_3") (pintype "input"))
      (node (ref "R30") (pin "2") (pinfunction "BOT_2") (pintype "passive"))
    )
    (net (code "52") (name "Net-(Q6-B)") (class "Default")
      (node (ref "Q6") (pin "2") (pinfunction "B_2") (pintype "input"))
      (node (ref "R16") (pin "2") (pinfunction "BOT_2") (pintype "passive"))
      (node (ref "R36") (pin "1") (pinfunction "TOP_1") (pintype "passive"))
    )
    (net (code "53") (name "Net-(Q6-C)") (class "Default")
      (node (ref "Q6") (pin "3") (pinfunction "C_3") (pintype "input"))
      (node (ref "R32") (pin "2") (pinfunction "BOT_2") (pintype "passive"))
    )
    (net (code "54") (name "Net-(Q7-B)") (class "Default")
      (node (ref "Q7") (pin "2") (pinfunction "B_2") (pintype "input"))
      (node (ref "R21") (pin "1") (pinfunction "TOP_1") (pintype "passive"))
      (node (ref "R41") (pin "2") (pinfunction "BOT_2") (pintype "passive"))
    )
    (net (code "55") (name "Net-(Q7-C)") (class "Default")
      (node (ref "Q7") (pin "3") (pinfunction "C_3") (pintype "input"))
      (node (ref "R33") (pin "2") (pinfunction "BOT_2") (pintype "passive"))
    )
    (net (code "56") (name "Net-(Q8-B)") (class "Default")
      (node (ref "Q8") (pin "2") (pinfunction "B_2") (pintype "input"))
      (node (ref "R22") (pin "1") (pinfunction "TOP_1") (pintype "passive"))
      (node (ref "R42") (pin "2") (pinfunction "BOT_2") (pintype "passive"))
    )
    (net (code "57") (name "Net-(Q8-C)") (class "Default")
      (node (ref "Q8") (pin "3") (pinfunction "C_3") (pintype "input"))
      (node (ref "R34") (pin "2") (pinfunction "BOT_2") (pintype "passive"))
    )
    (net (code "58") (name "Net-(Q9-B)") (class "Default")
      (node (ref "Q9") (pin "2") (pinfunction "B_2") (pintype "input"))
      (node (ref "R23") (pin "1") (pinfunction "TOP_1") (pintype "passive"))
      (node (ref "R43") (pin "2") (pinfunction "BOT_2") (pintype "passive"))
    )
    (net (code "59") (name "Net-(Q9-C)") (class "Default")
      (node (ref "Q9") (pin "3") (pinfunction "C_3") (pintype "input"))
      (node (ref "R35") (pin "2") (pinfunction "BOT_2") (pintype "passive"))
    )
    (net (code "60") (name "Net-(Q10-B)") (class "Default")
      (node (ref "Q10") (pin "2") (pinfunction "B_2") (pintype "input"))
      (node (ref "R24") (pin "1") (pinfunction "TOP_1") (pintype "passive"))
      (node (ref "R44") (pin "2") (pinfunction "BOT_2") (pintype "passive"))
    )
    (net (code "61") (name "Net-(Q10-C)") (class "Default")
      (node (ref "Q10") (pin "3") (pinfunction "C_3") (pintype "input"))
      (node (ref "R36") (pin "2") (pinfunction "BOT_2") (pintype "passive"))
    )
    (net (code "62") (name "Net-(R65-BOT)") (class "Default")
      (node (ref "R65") (pin "2") (pinfunction "BOT_2") (pintype "passive"))
      (node (ref "U4") (pin "6") (pinfunction "Y_6") (pintype "tri_state"))
    )
    (net (code "63") (name "Net-(R66-BOT)") (class "Default")
      (node (ref "R66") (pin "2") (pinfunction "BOT_2") (pintype "passive"))
      (node (ref "U4") (pin "11") (pinfunction "Y_11") (pintype "tri_state"))
    )
    (net (code "64") (name "Net-(R67-BOT)") (class "Default")
      (node (ref "R67") (pin "2") (pinfunction "BOT_2") (pintype "passive"))
      (node (ref "U5") (pin "6") (pinfunction "Y_6") (pintype "tri_state"))
    )
    (net (code "65") (name "Net-(R68-BOT)") (class "Default")
      (node (ref "R68") (pin "2") (pinfunction "BOT_2") (pintype "passive"))
      (node (ref "U5") (pin "11") (pinfunction "Y_11") (pintype "tri_state"))
    )
    (net (code "66") (name "Net-(R78-BOT)") (class "Default")
      (node (ref "R78") (pin "2") (pinfunction "BOT_2") (pintype "passive"))
      (node (ref "U5") (pin "9") (pinfunction "A_9") (pintype "input"))
    )
    (net (code "67") (name "Net-(R80-BOT)") (class "Default")
      (node (ref "R80") (pin "2") (pinfunction "BOT_2") (pintype "passive"))
      (node (ref "U4") (pin "2") (pinfunction "A_2") (pintype "input"))
    )
    (net (code "68") (name "Net-(R82-BOT)") (class "Default")
      (node (ref "R82") (pin "2") (pinfunction "BOT_2") (pintype "passive"))
      (node (ref "U4") (pin "9") (pinfunction "A_9") (pintype "input"))
    )
    (net (code "69") (name "Net-(R84-BOT)") (class "Default")
      (node (ref "R84") (pin "2") (pinfunction "BOT_2") (pintype "passive"))
      (node (ref "U5") (pin "2") (pinfunction "A_2") (pintype "input"))
    )
    (net (code "70") (name "RXINA") (class "Default")
      (node (ref "R74") (pin "2") (pinfunction "BOT_2") (pintype "passive"))
      (node (ref "U4") (pin "3") (pinfunction "Y_3") (pintype "tri_state"))
    )
    (net (code "71") (name "RXINA_EN") (class "Default")
      (node (ref "U4") (pin "1") (pinfunction "~{G}_1") (pintype "input"))
      (node (ref "U4") (pin "4") (pinfunction "~{G}_4") (pintype "input"))
    )
    (net (code "72") (name "RXINB") (class "Default")
      (node (ref "R75") (pin "2") (pinfunction "BOT_2") (pintype "passive"))
      (node (ref "U4") (pin "8") (pinfunction "Y_8") (pintype "tri_state"))
    )
    (net (code "73") (name "RXINB_EN") (class "Default")
      (node (ref "U4") (pin "10") (pinfunction "~{G}_10") (pintype "input"))
      (node (ref "U4") (pin "13") (pinfunction "~{G}_13") (pintype "input"))
    )
    (net (code "74") (name "RXINC") (class "Default")
      (node (ref "R76") (pin "2") (pinfunction "BOT_2") (pintype "passive"))
      (node (ref "U5") (pin "3") (pinfunction "Y_3") (pintype "tri_state"))
    )
    (net (code "75") (name "RXINC_EN") (class "Default")
      (node (ref "U5") (pin "1") (pinfunction "~{G}_1") (pintype "input"))
      (node (ref "U5") (pin "4") (pinfunction "~{G}_4") (pintype "input"))
    )
    (net (code "76") (name "RXIND") (class "Default")
      (node (ref "R73") (pin "2") (pinfunction "BOT_2") (pintype "passive"))
      (node (ref "U5") (pin "8") (pinfunction "Y_8") (pintype "tri_state"))
    )
    (net (code "77") (name "RXIND_EN") (class "Default")
      (node (ref "U5") (pin "10") (pinfunction "~{G}_10") (pintype "input"))
      (node (ref "U5") (pin "13") (pinfunction "~{G}_13") (pintype "input"))
    )
    (net (code "78") (name "TXINA") (class "Default")
      (node (ref "U4") (pin "5") (pinfunction "A_5") (pintype "input"))
    )
    (net (code "79") (name "TXINB") (class "Default")
      (node (ref "U4") (pin "12") (pinfunction "A_12") (pintype "input"))
    )
    (net (code "80") (name "TXINC") (class "Default")
      (node (ref "U5") (pin "5") (pinfunction "A_5") (pintype "input"))
    )
    (net (code "81") (name "TXIND") (class "Default")
      (node (ref "U5") (pin "12") (pinfunction "A_12") (pintype "input"))
    )
    (net (code "82") (name "V9") (class "Default")
      (node (ref "F1") (pin "2") (pinfunction "2_2") (pintype "passive"))
      (node (ref "Q3") (pin "1") (pinfunction "E_1") (pintype "input"))
      (node (ref "Q4") (pin "1") (pinfunction "E_1") (pintype "input"))
      (node (ref "Q5") (pin "1") (pinfunction "E_1") (pintype "input"))
      (node (ref "Q6") (pin "1") (pinfunction "E_1") (pintype "input"))
      (node (ref "R13") (pin "1") (pinfunction "TOP_1") (pintype "passive"))
      (node (ref "R14") (pin "1") (pinfunction "TOP_1") (pintype "passive"))
      (node (ref "R15") (pin "1") (pinfunction "TOP_1") (pintype "passive"))
      (node (ref "R16") (pin "1") (pinfunction "TOP_1") (pintype "passive"))
    )
    (net (code "83") (name "V33") (class "Default")
      (node (ref "C24") (pin "1") (pinfunction "1_1") (pintype "passive"))
      (node (ref "C26") (pin "1") (pinfunction "1_1") (pintype "passive"))
      (node (ref "C28") (pin "1") (pinfunction "1_1") (pintype "passive"))
      (node (ref "C30") (pin "1") (pinfunction "1_1") (pintype "passive"))
      (node (ref "D1") (pin "3") (pinfunction "K_3") (pintype "passive"))
      (node (ref "D2") (pin "3") (pinfunction "K_3") (pintype "passive"))
      (node (ref "D3") (pin "3") (pinfunction "K_3") (pintype "passive"))
      (node (ref "D4") (pin "3") (pinfunction "K_3") (pintype "passive"))
      (node (ref "R17") (pin "1") (pinfunction "TOP_1") (pintype "passive"))
      (node (ref "R18") (pin "1") (pinfunction "TOP_1") (pintype "passive"))
      (node (ref "R19") (pin "1") (pinfunction "TOP_1") (pintype "passive"))
      (node (ref "R20") (pin "1") (pinfunction "TOP_1") (pintype "passive"))
      (node (ref "R49") (pin "1") (pinfunction "TOP_1") (pintype "passive"))
      (node (ref "R51") (pin "1") (pinfunction "TOP_1") (pintype "passive"))
      (node (ref "R53") (pin "1") (pinfunction "TOP_1") (pintype "passive"))
      (node (ref "R55") (pin "1") (pinfunction "TOP_1") (pintype "passive"))
      (node (ref "R61") (pin "1") (pinfunction "TOP_1") (pintype "passive"))
      (node (ref "R62") (pin "1") (pinfunction "TOP_1") (pintype "passive"))
      (node (ref "R63") (pin "1") (pinfunction "TOP_1") (pintype "passive"))
      (node (ref "R64") (pin "1") (pinfunction "TOP_1") (pintype "passive"))
      (node (ref "R73") (pin "1") (pinfunction "TOP_1") (pintype "passive"))
      (node (ref "R74") (pin "1") (pinfunction "TOP_1") (pintype "passive"))
      (node (ref "R75") (pin "1") (pinfunction "TOP_1") (pintype "passive"))
      (node (ref "R76") (pin "1") (pinfunction "TOP_1") (pintype "passive"))
      (node (ref "U4") (pin "14") (pinfunction "VCC_14") (pintype "power_in"))
      (node (ref "U5") (pin "14") (pinfunction "VCC_14") (pintype "power_in"))
    )
    (net (code "84") (name "VBAT") (class "Default")
      (node (ref "F1") (pin "1") (pinfunction "1_1") (pintype "passive"))
    )
    (net (code "85") (name "VCCEXT") (class "Default")
      (node (ref "J5") (pin "4") (pinfunction "4_4") (pintype "passive"))
      (node (ref "J6") (pin "4") (pinfunction "4_4") (pintype "passive"))
      (node (ref "J7") (pin "4") (pinfunction "4_4") (pintype "passive"))
      (node (ref "J8") (pin "4") (pinfunction "4_4") (pintype "passive"))
    )
  )
)
